# MASTER.net
KiCad netlist of a schematic drawn in EAGLE
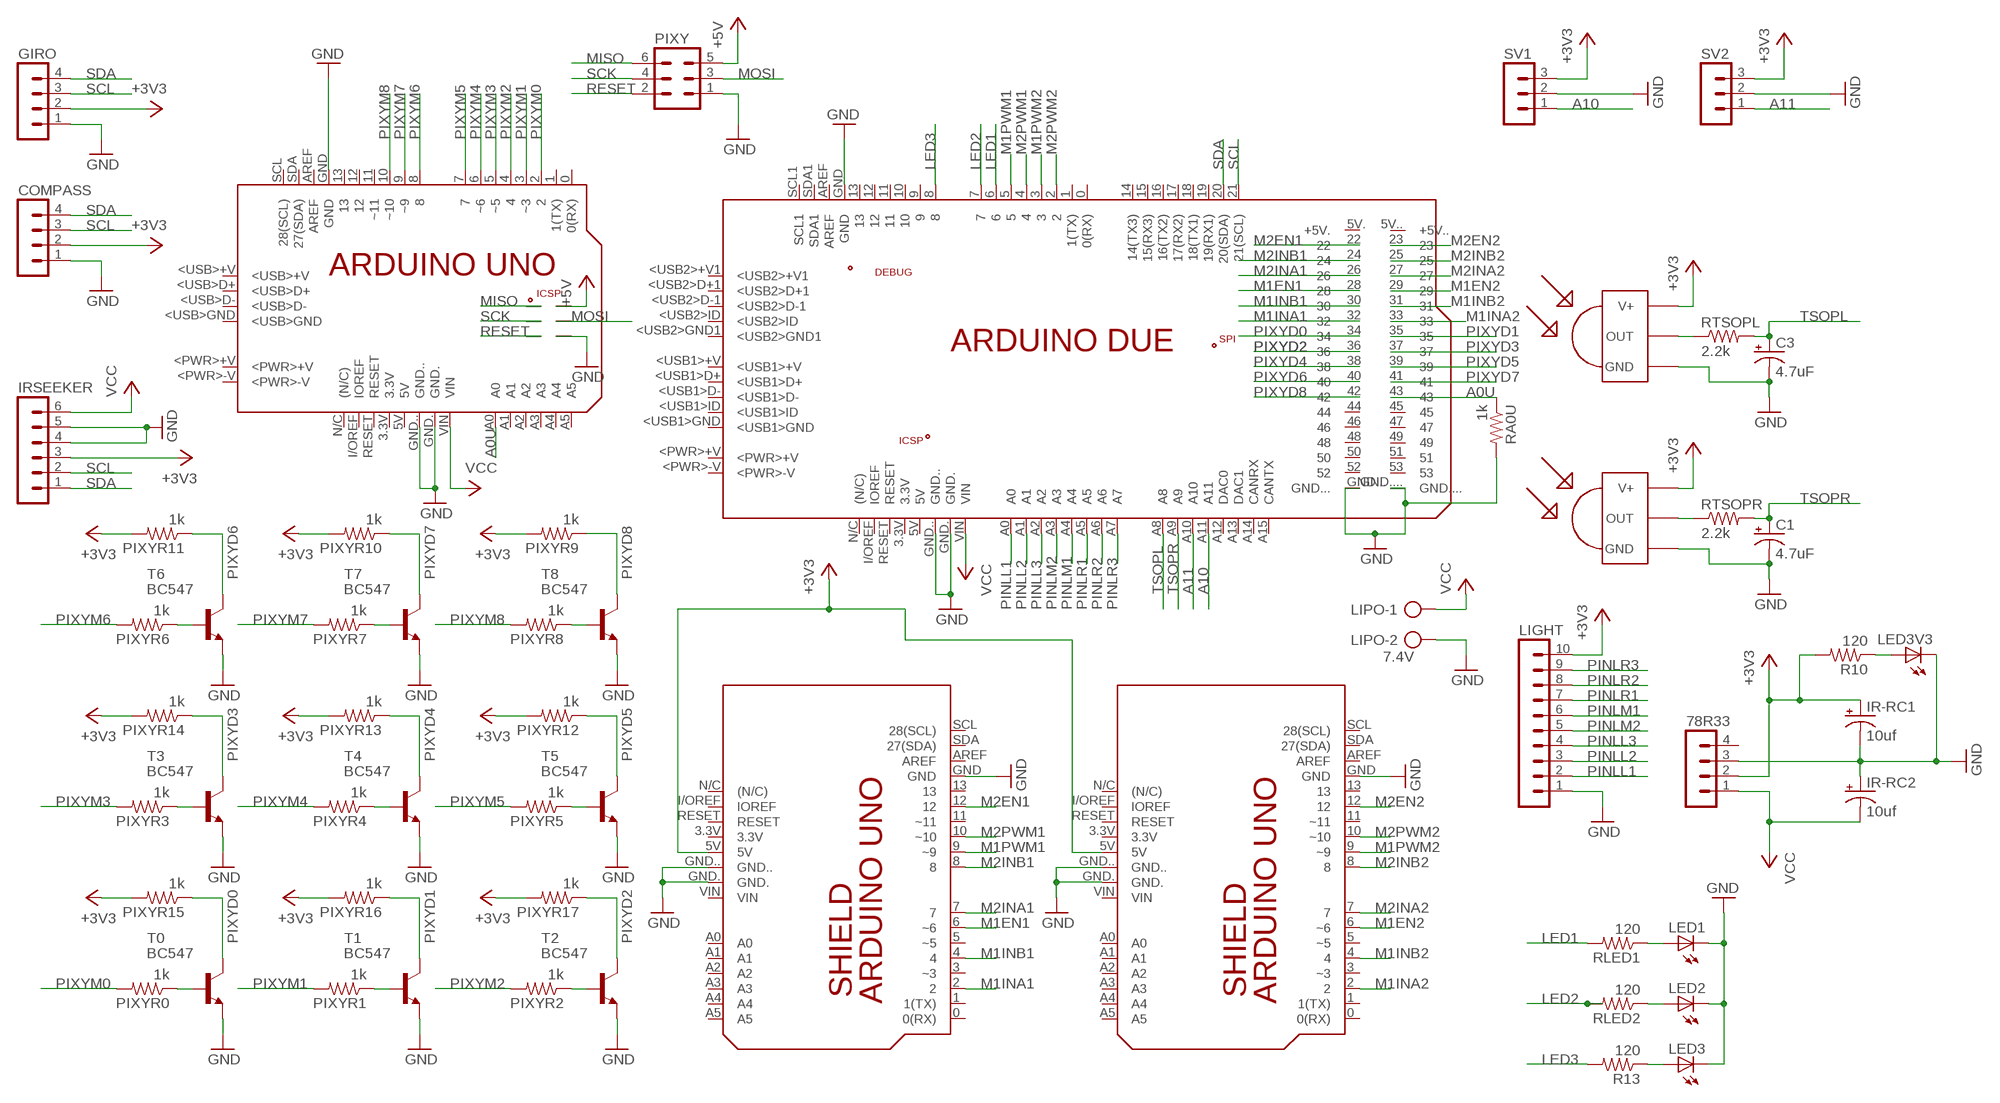
[diagram p0: schematic, sheet 1]

(export (version "E")
  (design (tool "Eeschema 10.0.6"))
  (components
    (comp (ref "78R33")
      (value "MA04-1")
      (footprint "eagle-import:MA04-1")
      (libsource (lib "eagle-import") (part "MA04-1"))
    )
    (comp (ref "C1")
      (value "4.7uF")
      (footprint "eagle-import:E5-6")
      (libsource (lib "eagle-import") (part "CPOL-USE5-6"))
    )
    (comp (ref "C3")
      (value "4.7uF")
      (footprint "eagle-import:E5-6")
      (libsource (lib "eagle-import") (part "CPOL-USE5-6"))
    )
    (comp (ref "COMPASS")
      (value "MA04-1")
      (footprint "eagle-import:MA04-1")
      (libsource (lib "eagle-import") (part "MA04-1"))
    )
    (comp (ref "GIRO")
      (value "MA04-1")
      (footprint "eagle-import:MA04-1")
      (libsource (lib "eagle-import") (part "MA04-1"))
    )
    (comp (ref "IR-RC1")
      (value "10uf")
      (footprint "eagle-import:E5-6")
      (libsource (lib "eagle-import") (part "CPOL-USE5-6"))
    )
    (comp (ref "IR-RC2")
      (value "10uf")
      (footprint "eagle-import:E5-6")
      (libsource (lib "eagle-import") (part "CPOL-USE5-6"))
    )
    (comp (ref "IRSEEKER")
      (value "MA06-1")
      (footprint "eagle-import:MA06-1")
      (libsource (lib "eagle-import") (part "MA06-1"))
    )
    (comp (ref "LED1")
      (value "LED5MM")
      (footprint "eagle-import:LED5MM")
      (libsource (lib "eagle-import") (part "LED5MM"))
    )
    (comp (ref "LED2")
      (value "LED5MM")
      (footprint "eagle-import:LED5MM")
      (libsource (lib "eagle-import") (part "LED5MM"))
    )
    (comp (ref "LED3")
      (value "LED5MM")
      (footprint "eagle-import:LED5MM")
      (libsource (lib "eagle-import") (part "LED5MM"))
    )
    (comp (ref "LED3V3")
      (value "LED5MM")
      (footprint "eagle-import:LED5MM")
      (libsource (lib "eagle-import") (part "LED5MM"))
    )
    (comp (ref "LIGHT")
      (value "MA10-1")
      (footprint "eagle-import:MA10-1")
      (libsource (lib "eagle-import") (part "MA10-1"))
    )
    (comp (ref "LIPO")
      (value "7.4V")
      (footprint "eagle-import:AK500_2")
      (libsource (lib "eagle-import") (part "AK500/2"))
    )
    (comp (ref "PCB3")
      (value "ARDUINO_DUE")
      (footprint "eagle-import:ARDUINO_DUE")
      (libsource (lib "eagle-import") (part "ARDUINO_DUE"))
    )
    (comp (ref "PCB4")
      (value "ARDUINO_UNO")
      (footprint "eagle-import:ARDUINO_UNO")
      (libsource (lib "eagle-import") (part "ARDUINO_UNO"))
    )
    (comp (ref "PIXY")
      (value "MA03-2")
      (footprint "eagle-import:MA03-2")
      (libsource (lib "eagle-import") (part "MA03-2"))
    )
    (comp (ref "PIXYR0")
      (value "1k")
      (footprint "eagle-import:0411_15")
      (libsource (lib "eagle-import") (part "R-US_0411/15"))
    )
    (comp (ref "PIXYR1")
      (value "1k")
      (footprint "eagle-import:0411_15")
      (libsource (lib "eagle-import") (part "R-US_0411/15"))
    )
    (comp (ref "PIXYR2")
      (value "1k")
      (footprint "eagle-import:0411_15")
      (libsource (lib "eagle-import") (part "R-US_0411/15"))
    )
    (comp (ref "PIXYR3")
      (value "1k")
      (footprint "eagle-import:0411_15")
      (libsource (lib "eagle-import") (part "R-US_0411/15"))
    )
    (comp (ref "PIXYR4")
      (value "1k")
      (footprint "eagle-import:0411_15")
      (libsource (lib "eagle-import") (part "R-US_0411/15"))
    )
    (comp (ref "PIXYR5")
      (value "1k")
      (footprint "eagle-import:0411_15")
      (libsource (lib "eagle-import") (part "R-US_0411/15"))
    )
    (comp (ref "PIXYR6")
      (value "1k")
      (footprint "eagle-import:0411_15")
      (libsource (lib "eagle-import") (part "R-US_0411/15"))
    )
    (comp (ref "PIXYR7")
      (value "1k")
      (footprint "eagle-import:0411_15")
      (libsource (lib "eagle-import") (part "R-US_0411/15"))
    )
    (comp (ref "PIXYR8")
      (value "1k")
      (footprint "eagle-import:0411_15")
      (libsource (lib "eagle-import") (part "R-US_0411/15"))
    )
    (comp (ref "PIXYR9")
      (value "1k")
      (footprint "eagle-import:0411_15")
      (libsource (lib "eagle-import") (part "R-US_0411/15"))
    )
    (comp (ref "PIXYR10")
      (value "1k")
      (footprint "eagle-import:0411_15")
      (libsource (lib "eagle-import") (part "R-US_0411/15"))
    )
    (comp (ref "PIXYR11")
      (value "1k")
      (footprint "eagle-import:0411_15")
      (libsource (lib "eagle-import") (part "R-US_0411/15"))
    )
    (comp (ref "PIXYR12")
      (value "1k")
      (footprint "eagle-import:0411_15")
      (libsource (lib "eagle-import") (part "R-US_0411/15"))
    )
    (comp (ref "PIXYR13")
      (value "1k")
      (footprint "eagle-import:0411_15")
      (libsource (lib "eagle-import") (part "R-US_0411/15"))
    )
    (comp (ref "PIXYR14")
      (value "1k")
      (footprint "eagle-import:0411_15")
      (libsource (lib "eagle-import") (part "R-US_0411/15"))
    )
    (comp (ref "PIXYR15")
      (value "1k")
      (footprint "eagle-import:0411_15")
      (libsource (lib "eagle-import") (part "R-US_0411/15"))
    )
    (comp (ref "PIXYR16")
      (value "1k")
      (footprint "eagle-import:0411_15")
      (libsource (lib "eagle-import") (part "R-US_0411/15"))
    )
    (comp (ref "PIXYR17")
      (value "1k")
      (footprint "eagle-import:0411_15")
      (libsource (lib "eagle-import") (part "R-US_0411/15"))
    )
    (comp (ref "PUENTE")
      (value "SHIELD_UNO")
      (footprint "eagle-import:SHIELD_UNO")
      (libsource (lib "eagle-import") (part "SHIELD_UNO"))
    )
    (comp (ref "PUENTE2")
      (value "SHIELD_UNO")
      (footprint "eagle-import:SHIELD_UNO")
      (libsource (lib "eagle-import") (part "SHIELD_UNO"))
    )
    (comp (ref "R10")
      (value "120")
      (footprint "eagle-import:0411_15")
      (libsource (lib "eagle-import") (part "R-US_0411/15"))
    )
    (comp (ref "R13")
      (value "120")
      (footprint "eagle-import:0411_15")
      (libsource (lib "eagle-import") (part "R-US_0411/15"))
    )
    (comp (ref "RA0U")
      (value "1k")
      (footprint "eagle-import:0411_15")
      (libsource (lib "eagle-import") (part "R-US_0411/15"))
    )
    (comp (ref "RLED1")
      (value "120")
      (footprint "eagle-import:0411_15")
      (libsource (lib "eagle-import") (part "R-US_0411/15"))
    )
    (comp (ref "RLED2")
      (value "120")
      (footprint "eagle-import:0411_15")
      (libsource (lib "eagle-import") (part "R-US_0411/15"))
    )
    (comp (ref "RTSOPL")
      (value "2.2k")
      (footprint "eagle-import:0411_15")
      (libsource (lib "eagle-import") (part "R-US_0411/15"))
    )
    (comp (ref "RTSOPR")
      (value "2.2k")
      (footprint "eagle-import:0411_15")
      (libsource (lib "eagle-import") (part "R-US_0411/15"))
    )
    (comp (ref "SV1")
      (value "MA03-1")
      (footprint "eagle-import:MA03-1")
      (libsource (lib "eagle-import") (part "MA03-1"))
    )
    (comp (ref "SV2")
      (value "MA03-1")
      (footprint "eagle-import:MA03-1")
      (libsource (lib "eagle-import") (part "MA03-1"))
    )
    (comp (ref "T0")
      (value "BC547")
      (footprint "eagle-import:TO92")
      (libsource (lib "eagle-import") (part "BC547"))
    )
    (comp (ref "T1")
      (value "BC547")
      (footprint "eagle-import:TO92")
      (libsource (lib "eagle-import") (part "BC547"))
    )
    (comp (ref "T2")
      (value "BC547")
      (footprint "eagle-import:TO92")
      (libsource (lib "eagle-import") (part "BC547"))
    )
    (comp (ref "T3")
      (value "BC547")
      (footprint "eagle-import:TO92")
      (libsource (lib "eagle-import") (part "BC547"))
    )
    (comp (ref "T4")
      (value "BC547")
      (footprint "eagle-import:TO92")
      (libsource (lib "eagle-import") (part "BC547"))
    )
    (comp (ref "T5")
      (value "BC547")
      (footprint "eagle-import:TO92")
      (libsource (lib "eagle-import") (part "BC547"))
    )
    (comp (ref "T6")
      (value "BC547")
      (footprint "eagle-import:TO92")
      (libsource (lib "eagle-import") (part "BC547"))
    )
    (comp (ref "T7")
      (value "BC547")
      (footprint "eagle-import:TO92")
      (libsource (lib "eagle-import") (part "BC547"))
    )
    (comp (ref "T8")
      (value "BC547")
      (footprint "eagle-import:TO92")
      (libsource (lib "eagle-import") (part "BC547"))
    )
    (comp (ref "TSOPL")
      (value "TSOP2240")
      (footprint "eagle-import:TSOP22XX")
      (libsource (lib "eagle-import") (part "TSOP2240"))
    )
    (comp (ref "TSOPR")
      (value "TSOP2240")
      (footprint "eagle-import:TSOP22XX")
      (libsource (lib "eagle-import") (part "TSOP2240"))
    )
  )
  (nets
    (net (code "1") (name "+3V3") (class "Default")
      (node (ref "78R33") (pin "2") (pinfunction "2_2") (pintype "passive"))
      (node (ref "COMPASS") (pin "2") (pinfunction "2_2") (pintype "passive"))
      (node (ref "GIRO") (pin "2") (pinfunction "2_2") (pintype "passive"))
      (node (ref "IR-RC1") (pin "+") (pinfunction "+_+") (pintype "passive"))
      (node (ref "IRSEEKER") (pin "3") (pinfunction "3_3") (pintype "passive"))
      (node (ref "LIGHT") (pin "10") (pinfunction "10_10") (pintype "passive"))
      (node (ref "PIXYR10") (pin "2") (pinfunction "2_2") (pintype "passive"))
      (node (ref "PIXYR11") (pin "2") (pinfunction "2_2") (pintype "passive"))
      (node (ref "PIXYR12") (pin "2") (pinfunction "2_2") (pintype "passive"))
      (node (ref "PIXYR13") (pin "2") (pinfunction "2_2") (pintype "passive"))
      (node (ref "PIXYR14") (pin "2") (pinfunction "2_2") (pintype "passive"))
      (node (ref "PIXYR15") (pin "2") (pinfunction "2_2") (pintype "passive"))
      (node (ref "PIXYR16") (pin "2") (pinfunction "2_2") (pintype "passive"))
      (node (ref "PIXYR17") (pin "2") (pinfunction "2_2") (pintype "passive"))
      (node (ref "PIXYR9") (pin "2") (pinfunction "2_2") (pintype "passive"))
      (node (ref "PUENTE") (pin "5V") (pinfunction "5V_5V") (pintype "bidirectional"))
      (node (ref "PUENTE2") (pin "5V") (pinfunction "5V_5V") (pintype "bidirectional"))
      (node (ref "R10") (pin "2") (pinfunction "2_2") (pintype "passive"))
      (node (ref "SV1") (pin "3") (pinfunction "3_3") (pintype "passive"))
      (node (ref "SV2") (pin "3") (pinfunction "3_3") (pintype "passive"))
      (node (ref "TSOPL") (pin "VCC") (pinfunction "V+_VCC") (pintype "bidirectional"))
      (node (ref "TSOPR") (pin "VCC") (pinfunction "V+_VCC") (pintype "bidirectional"))
    )
    (net (code "2") (name "+5V") (class "Default")
      (node (ref "PCB4") (pin "+5V") (pinfunction "+5V_+5V") (pintype "bidirectional"))
      (node (ref "PIXY") (pin "5") (pinfunction "5_5") (pintype "passive"))
    )
    (net (code "3") (name "/A0U") (class "Default")
      (node (ref "PCB3") (pin "43") (pinfunction "43_43") (pintype "bidirectional"))
      (node (ref "PCB4") (pin "A0") (pinfunction "A0_A0") (pintype "bidirectional"))
      (node (ref "RA0U") (pin "1") (pinfunction "1_1") (pintype "passive"))
    )
    (net (code "4") (name "/A10") (class "Default")
      (node (ref "PCB3") (pin "A11") (pinfunction "A11_A11") (pintype "bidirectional"))
      (node (ref "SV1") (pin "1") (pinfunction "1_1") (pintype "passive"))
    )
    (net (code "5") (name "/A11") (class "Default")
      (node (ref "PCB3") (pin "A10") (pinfunction "A10_A10") (pintype "bidirectional"))
      (node (ref "SV2") (pin "1") (pinfunction "1_1") (pintype "passive"))
    )
    (net (code "6") (name "/LED1") (class "Default")
      (node (ref "PCB3") (pin "6") (pinfunction "6_6") (pintype "bidirectional"))
      (node (ref "RLED1") (pin "2") (pinfunction "2_2") (pintype "passive"))
    )
    (net (code "7") (name "/LED2") (class "Default")
      (node (ref "PCB3") (pin "7") (pinfunction "7_7") (pintype "bidirectional"))
      (node (ref "RLED2") (pin "2") (pinfunction "2_2") (pintype "passive"))
    )
    (net (code "8") (name "/LED3") (class "Default")
      (node (ref "PCB3") (pin "8") (pinfunction "8_8") (pintype "bidirectional"))
      (node (ref "R13") (pin "2") (pinfunction "2_2") (pintype "passive"))
    )
    (net (code "9") (name "/M1EN1") (class "Default")
      (node (ref "PCB3") (pin "28") (pinfunction "28_28") (pintype "bidirectional"))
      (node (ref "PUENTE") (pin "6") (pinfunction "~{6}_6") (pintype "bidirectional"))
    )
    (net (code "10") (name "/M1EN2") (class "Default")
      (node (ref "PCB3") (pin "29") (pinfunction "29_29") (pintype "bidirectional"))
      (node (ref "PUENTE2") (pin "6") (pinfunction "~{6}_6") (pintype "bidirectional"))
    )
    (net (code "11") (name "/M1INA1") (class "Default")
      (node (ref "PCB3") (pin "32") (pinfunction "32_32") (pintype "bidirectional"))
      (node (ref "PUENTE") (pin "2") (pinfunction "2_2") (pintype "bidirectional"))
    )
    (net (code "12") (name "/M1INA2") (class "Default")
      (node (ref "PCB3") (pin "33") (pinfunction "33_33") (pintype "bidirectional"))
      (node (ref "PUENTE2") (pin "2") (pinfunction "2_2") (pintype "bidirectional"))
    )
    (net (code "13") (name "/M1INB1") (class "Default")
      (node (ref "PCB3") (pin "30") (pinfunction "30_30") (pintype "bidirectional"))
      (node (ref "PUENTE") (pin "4") (pinfunction "4_4") (pintype "bidirectional"))
    )
    (net (code "14") (name "/M1INB2") (class "Default")
      (node (ref "PCB3") (pin "31") (pinfunction "31_31") (pintype "bidirectional"))
      (node (ref "PUENTE2") (pin "4") (pinfunction "4_4") (pintype "bidirectional"))
    )
    (net (code "15") (name "/M1PWM1") (class "Default")
      (node (ref "PCB3") (pin "5") (pinfunction "5_5") (pintype "bidirectional"))
      (node (ref "PUENTE") (pin "9") (pinfunction "~{9}_9") (pintype "bidirectional"))
    )
    (net (code "16") (name "/M1PWM2") (class "Default")
      (node (ref "PCB3") (pin "3") (pinfunction "3_3") (pintype "bidirectional"))
      (node (ref "PUENTE2") (pin "9") (pinfunction "~{9}_9") (pintype "bidirectional"))
    )
    (net (code "17") (name "/M2EN1") (class "Default")
      (node (ref "PCB3") (pin "22") (pinfunction "22_22") (pintype "bidirectional"))
      (node (ref "PUENTE") (pin "12") (pinfunction "12_12") (pintype "bidirectional"))
    )
    (net (code "18") (name "/M2EN2") (class "Default")
      (node (ref "PCB3") (pin "23") (pinfunction "23_23") (pintype "bidirectional"))
      (node (ref "PUENTE2") (pin "12") (pinfunction "12_12") (pintype "bidirectional"))
    )
    (net (code "19") (name "/M2INA1") (class "Default")
      (node (ref "PCB3") (pin "26") (pinfunction "26_26") (pintype "bidirectional"))
      (node (ref "PUENTE") (pin "7") (pinfunction "7_7") (pintype "bidirectional"))
    )
    (net (code "20") (name "/M2INA2") (class "Default")
      (node (ref "PCB3") (pin "27") (pinfunction "27_27") (pintype "bidirectional"))
      (node (ref "PUENTE2") (pin "7") (pinfunction "7_7") (pintype "bidirectional"))
    )
    (net (code "21") (name "/M2INB1") (class "Default")
      (node (ref "PCB3") (pin "24") (pinfunction "24_24") (pintype "bidirectional"))
      (node (ref "PUENTE") (pin "8") (pinfunction "8_8") (pintype "bidirectional"))
    )
    (net (code "22") (name "/M2INB2") (class "Default")
      (node (ref "PCB3") (pin "25") (pinfunction "25_25") (pintype "bidirectional"))
      (node (ref "PUENTE2") (pin "8") (pinfunction "8_8") (pintype "bidirectional"))
    )
    (net (code "23") (name "/M2PWM1") (class "Default")
      (node (ref "PCB3") (pin "4") (pinfunction "4_4") (pintype "bidirectional"))
      (node (ref "PUENTE") (pin "10") (pinfunction "~{10}_10") (pintype "bidirectional"))
    )
    (net (code "24") (name "/M2PWM2") (class "Default")
      (node (ref "PCB3") (pin "2") (pinfunction "2_2") (pintype "bidirectional"))
      (node (ref "PUENTE2") (pin "10") (pinfunction "~{10}_10") (pintype "bidirectional"))
    )
    (net (code "25") (name "/MISO") (class "Default")
      (node (ref "PCB4") (pin "MISO") (pinfunction "MISO_MISO") (pintype "bidirectional"))
      (node (ref "PIXY") (pin "6") (pinfunction "6_6") (pintype "passive"))
    )
    (net (code "26") (name "/MOSI") (class "Default")
      (node (ref "PCB4") (pin "MOSI") (pinfunction "MOSI_MOSI") (pintype "bidirectional"))
      (node (ref "PIXY") (pin "3") (pinfunction "3_3") (pintype "passive"))
    )
    (net (code "27") (name "/PINLL1") (class "Default")
      (node (ref "LIGHT") (pin "2") (pinfunction "2_2") (pintype "passive"))
      (node (ref "PCB3") (pin "A0") (pinfunction "A0_A0") (pintype "bidirectional"))
    )
    (net (code "28") (name "/PINLL2") (class "Default")
      (node (ref "LIGHT") (pin "3") (pinfunction "3_3") (pintype "passive"))
      (node (ref "PCB3") (pin "A1") (pinfunction "A1_A1") (pintype "bidirectional"))
    )
    (net (code "29") (name "/PINLL3") (class "Default")
      (node (ref "LIGHT") (pin "4") (pinfunction "4_4") (pintype "passive"))
      (node (ref "PCB3") (pin "A2") (pinfunction "A2_A2") (pintype "bidirectional"))
    )
    (net (code "30") (name "/PINLM1") (class "Default")
      (node (ref "LIGHT") (pin "6") (pinfunction "6_6") (pintype "passive"))
      (node (ref "PCB3") (pin "A4") (pinfunction "A4_A4") (pintype "bidirectional"))
    )
    (net (code "31") (name "/PINLM2") (class "Default")
      (node (ref "LIGHT") (pin "5") (pinfunction "5_5") (pintype "passive"))
      (node (ref "PCB3") (pin "A3") (pinfunction "A3_A3") (pintype "bidirectional"))
    )
    (net (code "32") (name "/PINLR1") (class "Default")
      (node (ref "LIGHT") (pin "7") (pinfunction "7_7") (pintype "passive"))
      (node (ref "PCB3") (pin "A5") (pinfunction "A5_A5") (pintype "bidirectional"))
    )
    (net (code "33") (name "/PINLR2") (class "Default")
      (node (ref "LIGHT") (pin "8") (pinfunction "8_8") (pintype "passive"))
      (node (ref "PCB3") (pin "A6") (pinfunction "A6_A6") (pintype "bidirectional"))
    )
    (net (code "34") (name "/PINLR3") (class "Default")
      (node (ref "LIGHT") (pin "9") (pinfunction "9_9") (pintype "passive"))
      (node (ref "PCB3") (pin "A7") (pinfunction "A7_A7") (pintype "bidirectional"))
    )
    (net (code "35") (name "/PIXYD0") (class "Default")
      (node (ref "PCB3") (pin "34") (pinfunction "34_34") (pintype "bidirectional"))
      (node (ref "PIXYR15") (pin "1") (pinfunction "1_1") (pintype "passive"))
      (node (ref "T0") (pin "3") (pinfunction "C_3") (pintype "passive"))
    )
    (net (code "36") (name "/PIXYD1") (class "Default")
      (node (ref "PCB3") (pin "35") (pinfunction "35_35") (pintype "bidirectional"))
      (node (ref "PIXYR16") (pin "1") (pinfunction "1_1") (pintype "passive"))
      (node (ref "T1") (pin "3") (pinfunction "C_3") (pintype "passive"))
    )
    (net (code "37") (name "/PIXYD2") (class "Default")
      (node (ref "PCB3") (pin "36") (pinfunction "36_36") (pintype "bidirectional"))
      (node (ref "PIXYR17") (pin "1") (pinfunction "1_1") (pintype "passive"))
      (node (ref "T2") (pin "3") (pinfunction "C_3") (pintype "passive"))
    )
    (net (code "38") (name "/PIXYD3") (class "Default")
      (node (ref "PCB3") (pin "37") (pinfunction "37_37") (pintype "bidirectional"))
      (node (ref "PIXYR14") (pin "1") (pinfunction "1_1") (pintype "passive"))
      (node (ref "T3") (pin "3") (pinfunction "C_3") (pintype "passive"))
    )
    (net (code "39") (name "/PIXYD4") (class "Default")
      (node (ref "PCB3") (pin "38") (pinfunction "38_38") (pintype "bidirectional"))
      (node (ref "PIXYR13") (pin "1") (pinfunction "1_1") (pintype "passive"))
      (node (ref "T4") (pin "3") (pinfunction "C_3") (pintype "passive"))
    )
    (net (code "40") (name "/PIXYD5") (class "Default")
      (node (ref "PCB3") (pin "39") (pinfunction "39_39") (pintype "bidirectional"))
      (node (ref "PIXYR12") (pin "1") (pinfunction "1_1") (pintype "passive"))
      (node (ref "T5") (pin "3") (pinfunction "C_3") (pintype "passive"))
    )
    (net (code "41") (name "/PIXYD6") (class "Default")
      (node (ref "PCB3") (pin "40") (pinfunction "40_40") (pintype "bidirectional"))
      (node (ref "PIXYR11") (pin "1") (pinfunction "1_1") (pintype "passive"))
      (node (ref "T6") (pin "3") (pinfunction "C_3") (pintype "passive"))
    )
    (net (code "42") (name "/PIXYD7") (class "Default")
      (node (ref "PCB3") (pin "41") (pinfunction "41_41") (pintype "bidirectional"))
      (node (ref "PIXYR10") (pin "1") (pinfunction "1_1") (pintype "passive"))
      (node (ref "T7") (pin "3") (pinfunction "C_3") (pintype "passive"))
    )
    (net (code "43") (name "/PIXYD8") (class "Default")
      (node (ref "PCB3") (pin "42") (pinfunction "42_42") (pintype "bidirectional"))
      (node (ref "PIXYR9") (pin "1") (pinfunction "1_1") (pintype "passive"))
      (node (ref "T8") (pin "3") (pinfunction "C_3") (pintype "passive"))
    )
    (net (code "44") (name "/PIXYM0") (class "Default")
      (node (ref "PCB4") (pin "2") (pinfunction "2_2") (pintype "bidirectional"))
      (node (ref "PIXYR0") (pin "2") (pinfunction "2_2") (pintype "passive"))
    )
    (net (code "45") (name "/PIXYM1") (class "Default")
      (node (ref "PCB4") (pin "3") (pinfunction "~{3}_3") (pintype "bidirectional"))
      (node (ref "PIXYR1") (pin "2") (pinfunction "2_2") (pintype "passive"))
    )
    (net (code "46") (name "/PIXYM2") (class "Default")
      (node (ref "PCB4") (pin "4") (pinfunction "4_4") (pintype "bidirectional"))
      (node (ref "PIXYR2") (pin "2") (pinfunction "2_2") (pintype "passive"))
    )
    (net (code "47") (name "/PIXYM3") (class "Default")
      (node (ref "PCB4") (pin "5") (pinfunction "~{5}_5") (pintype "bidirectional"))
      (node (ref "PIXYR3") (pin "2") (pinfunction "2_2") (pintype "passive"))
    )
    (net (code "48") (name "/PIXYM4") (class "Default")
      (node (ref "PCB4") (pin "6") (pinfunction "~{6}_6") (pintype "bidirectional"))
      (node (ref "PIXYR4") (pin "2") (pinfunction "2_2") (pintype "passive"))
    )
    (net (code "49") (name "/PIXYM5") (class "Default")
      (node (ref "PCB4") (pin "7") (pinfunction "7_7") (pintype "bidirectional"))
      (node (ref "PIXYR5") (pin "2") (pinfunction "2_2") (pintype "passive"))
    )
    (net (code "50") (name "/PIXYM6") (class "Default")
      (node (ref "PCB4") (pin "8") (pinfunction "8_8") (pintype "bidirectional"))
      (node (ref "PIXYR6") (pin "2") (pinfunction "2_2") (pintype "passive"))
    )
    (net (code "51") (name "/PIXYM7") (class "Default")
      (node (ref "PCB4") (pin "9") (pinfunction "~{9}_9") (pintype "bidirectional"))
      (node (ref "PIXYR7") (pin "2") (pinfunction "2_2") (pintype "passive"))
    )
    (net (code "52") (name "/PIXYM8") (class "Default")
      (node (ref "PCB4") (pin "10") (pinfunction "~{10}_10") (pintype "bidirectional"))
      (node (ref "PIXYR8") (pin "2") (pinfunction "2_2") (pintype "passive"))
    )
    (net (code "53") (name "/RESET") (class "Default")
      (node (ref "PCB4") (pin "RESET.") (pinfunction "RESET._RESET.") (pintype "bidirectional"))
      (node (ref "PIXY") (pin "2") (pinfunction "2_2") (pintype "passive"))
    )
    (net (code "54") (name "/SCK") (class "Default")
      (node (ref "PCB4") (pin "SCK") (pinfunction "SCK_SCK") (pintype "bidirectional"))
      (node (ref "PIXY") (pin "4") (pinfunction "4_4") (pintype "passive"))
    )
    (net (code "55") (name "/SCL") (class "Default")
      (node (ref "COMPASS") (pin "3") (pinfunction "3_3") (pintype "passive"))
      (node (ref "GIRO") (pin "3") (pinfunction "3_3") (pintype "passive"))
      (node (ref "IRSEEKER") (pin "2") (pinfunction "2_2") (pintype "passive"))
      (node (ref "PCB3") (pin "21") (pinfunction "21(SCL)_21") (pintype "bidirectional"))
    )
    (net (code "56") (name "/SDA") (class "Default")
      (node (ref "COMPASS") (pin "4") (pinfunction "4_4") (pintype "passive"))
      (node (ref "GIRO") (pin "4") (pinfunction "4_4") (pintype "passive"))
      (node (ref "IRSEEKER") (pin "1") (pinfunction "1_1") (pintype "passive"))
      (node (ref "PCB3") (pin "20") (pinfunction "20(SDA)_20") (pintype "bidirectional"))
    )
    (net (code "57") (name "/TSOPL") (class "Default")
      (node (ref "C3") (pin "+") (pinfunction "+_+") (pintype "passive"))
      (node (ref "PCB3") (pin "A8") (pinfunction "A8_A8") (pintype "bidirectional"))
      (node (ref "RTSOPL") (pin "2") (pinfunction "2_2") (pintype "passive"))
    )
    (net (code "58") (name "/TSOPR") (class "Default")
      (node (ref "C1") (pin "+") (pinfunction "+_+") (pintype "passive"))
      (node (ref "PCB3") (pin "A9") (pinfunction "A9_A9") (pintype "bidirectional"))
      (node (ref "RTSOPR") (pin "2") (pinfunction "2_2") (pintype "passive"))
    )
    (net (code "59") (name "GND") (class "Default")
      (node (ref "78R33") (pin "3") (pinfunction "3_3") (pintype "passive"))
      (node (ref "C1") (pin "-") (pinfunction "-_-") (pintype "passive"))
      (node (ref "C3") (pin "-") (pinfunction "-_-") (pintype "passive"))
      (node (ref "COMPASS") (pin "1") (pinfunction "1_1") (pintype "passive"))
      (node (ref "GIRO") (pin "1") (pinfunction "1_1") (pintype "passive"))
      (node (ref "IR-RC1") (pin "-") (pinfunction "-_-") (pintype "passive"))
      (node (ref "IR-RC2") (pin "+") (pinfunction "+_+") (pintype "passive"))
      (node (ref "IRSEEKER") (pin "4") (pinfunction "4_4") (pintype "passive"))
      (node (ref "IRSEEKER") (pin "5") (pinfunction "5_5") (pintype "passive"))
      (node (ref "LED1") (pin "K") (pinfunction "C_K") (pintype "passive"))
      (node (ref "LED2") (pin "K") (pinfunction "C_K") (pintype "passive"))
      (node (ref "LED3") (pin "K") (pinfunction "C_K") (pintype "passive"))
      (node (ref "LED3V3") (pin "K") (pinfunction "C_K") (pintype "passive"))
      (node (ref "LIGHT") (pin "1") (pinfunction "1_1") (pintype "passive"))
      (node (ref "LIPO") (pin "2") (pinfunction "KL_2") (pintype "passive"))
      (node (ref "PCB3") (pin "GND") (pinfunction "GND_GND") (pintype "bidirectional"))
      (node (ref "PCB3") (pin "GND.") (pinfunction "GND._GND.") (pintype "bidirectional"))
      (node (ref "PCB3") (pin "GND..") (pinfunction "GND.._GND..") (pintype "bidirectional"))
      (node (ref "PCB3") (pin "GND...") (pinfunction "GND..._GND...") (pintype "bidirectional"))
      (node (ref "PCB3") (pin "GND....") (pinfunction "GND...._GND....") (pintype "bidirectional"))
      (node (ref "PCB4") (pin "GND") (pinfunction "GND_GND") (pintype "bidirectional"))
      (node (ref "PCB4") (pin "GND.") (pinfunction "GND._GND.") (pintype "bidirectional"))
      (node (ref "PCB4") (pin "GND..") (pinfunction "GND.._GND..") (pintype "bidirectional"))
      (node (ref "PCB4") (pin "GND_") (pinfunction "GND__GND_") (pintype "bidirectional"))
      (node (ref "PIXY") (pin "1") (pinfunction "1_1") (pintype "passive"))
      (node (ref "PUENTE") (pin "GND") (pinfunction "GND_GND") (pintype "bidirectional"))
      (node (ref "PUENTE") (pin "GND.") (pinfunction "GND._GND.") (pintype "bidirectional"))
      (node (ref "PUENTE") (pin "GND..") (pinfunction "GND.._GND..") (pintype "bidirectional"))
      (node (ref "PUENTE2") (pin "GND") (pinfunction "GND_GND") (pintype "bidirectional"))
      (node (ref "PUENTE2") (pin "GND.") (pinfunction "GND._GND.") (pintype "bidirectional"))
      (node (ref "PUENTE2") (pin "GND..") (pinfunction "GND.._GND..") (pintype "bidirectional"))
      (node (ref "RA0U") (pin "2") (pinfunction "2_2") (pintype "passive"))
      (node (ref "SV1") (pin "2") (pinfunction "2_2") (pintype "passive"))
      (node (ref "SV2") (pin "2") (pinfunction "2_2") (pintype "passive"))
      (node (ref "T0") (pin "1") (pinfunction "E_1") (pintype "passive"))
      (node (ref "T1") (pin "1") (pinfunction "E_1") (pintype "passive"))
      (node (ref "T2") (pin "1") (pinfunction "E_1") (pintype "passive"))
      (node (ref "T3") (pin "1") (pinfunction "E_1") (pintype "passive"))
      (node (ref "T4") (pin "1") (pinfunction "E_1") (pintype "passive"))
      (node (ref "T5") (pin "1") (pinfunction "E_1") (pintype "passive"))
      (node (ref "T6") (pin "1") (pinfunction "E_1") (pintype "passive"))
      (node (ref "T7") (pin "1") (pinfunction "E_1") (pintype "passive"))
      (node (ref "T8") (pin "1") (pinfunction "E_1") (pintype "passive"))
      (node (ref "TSOPL") (pin "GND") (pinfunction "GND_GND") (pintype "bidirectional"))
      (node (ref "TSOPR") (pin "GND") (pinfunction "GND_GND") (pintype "bidirectional"))
    )
    (net (code "60") (name "Net-(LED1-PadA)") (class "Default")
      (node (ref "LED1") (pin "A") (pinfunction "A_A") (pintype "passive"))
      (node (ref "RLED1") (pin "1") (pinfunction "1_1") (pintype "passive"))
    )
    (net (code "61") (name "Net-(LED2-PadA)") (class "Default")
      (node (ref "LED2") (pin "A") (pinfunction "A_A") (pintype "passive"))
      (node (ref "RLED2") (pin "1") (pinfunction "1_1") (pintype "passive"))
    )
    (net (code "62") (name "Net-(LED3-PadA)") (class "Default")
      (node (ref "LED3") (pin "A") (pinfunction "A_A") (pintype "passive"))
      (node (ref "R13") (pin "1") (pinfunction "1_1") (pintype "passive"))
    )
    (net (code "63") (name "Net-(LED3V3-PadA)") (class "Default")
      (node (ref "LED3V3") (pin "A") (pinfunction "A_A") (pintype "passive"))
      (node (ref "R10") (pin "1") (pinfunction "1_1") (pintype "passive"))
    )
    (net (code "64") (name "Net-(RTSOPL-Pad1)") (class "Default")
      (node (ref "RTSOPL") (pin "1") (pinfunction "1_1") (pintype "passive"))
      (node (ref "TSOPL") (pin "OUT") (pinfunction "OUT_OUT") (pintype "bidirectional"))
    )
    (net (code "65") (name "Net-(RTSOPR-Pad1)") (class "Default")
      (node (ref "RTSOPR") (pin "1") (pinfunction "1_1") (pintype "passive"))
      (node (ref "TSOPR") (pin "OUT") (pinfunction "OUT_OUT") (pintype "bidirectional"))
    )
    (net (code "66") (name "Net-(T0-B)") (class "Default")
      (node (ref "PIXYR0") (pin "1") (pinfunction "1_1") (pintype "passive"))
      (node (ref "T0") (pin "2") (pinfunction "B_2") (pintype "passive"))
    )
    (net (code "67") (name "Net-(T1-B)") (class "Default")
      (node (ref "PIXYR1") (pin "1") (pinfunction "1_1") (pintype "passive"))
      (node (ref "T1") (pin "2") (pinfunction "B_2") (pintype "passive"))
    )
    (net (code "68") (name "Net-(T2-B)") (class "Default")
      (node (ref "PIXYR2") (pin "1") (pinfunction "1_1") (pintype "passive"))
      (node (ref "T2") (pin "2") (pinfunction "B_2") (pintype "passive"))
    )
    (net (code "69") (name "Net-(T3-B)") (class "Default")
      (node (ref "PIXYR3") (pin "1") (pinfunction "1_1") (pintype "passive"))
      (node (ref "T3") (pin "2") (pinfunction "B_2") (pintype "passive"))
    )
    (net (code "70") (name "Net-(T4-B)") (class "Default")
      (node (ref "PIXYR4") (pin "1") (pinfunction "1_1") (pintype "passive"))
      (node (ref "T4") (pin "2") (pinfunction "B_2") (pintype "passive"))
    )
    (net (code "71") (name "Net-(T5-B)") (class "Default")
      (node (ref "PIXYR5") (pin "1") (pinfunction "1_1") (pintype "passive"))
      (node (ref "T5") (pin "2") (pinfunction "B_2") (pintype "passive"))
    )
    (net (code "72") (name "Net-(T6-B)") (class "Default")
      (node (ref "PIXYR6") (pin "1") (pinfunction "1_1") (pintype "passive"))
      (node (ref "T6") (pin "2") (pinfunction "B_2") (pintype "passive"))
    )
    (net (code "73") (name "Net-(T7-B)") (class "Default")
      (node (ref "PIXYR7") (pin "1") (pinfunction "1_1") (pintype "passive"))
      (node (ref "T7") (pin "2") (pinfunction "B_2") (pintype "passive"))
    )
    (net (code "74") (name "Net-(T8-B)") (class "Default")
      (node (ref "PIXYR8") (pin "1") (pinfunction "1_1") (pintype "passive"))
      (node (ref "T8") (pin "2") (pinfunction "B_2") (pintype "passive"))
    )
    (net (code "75") (name "VCC") (class "Default")
      (node (ref "78R33") (pin "1") (pinfunction "1_1") (pintype "passive"))
      (node (ref "IR-RC2") (pin "-") (pinfunction "-_-") (pintype "passive"))
      (node (ref "IRSEEKER") (pin "6") (pinfunction "6_6") (pintype "passive"))
      (node (ref "LIPO") (pin "1") (pinfunction "KL_1") (pintype "passive"))
      (node (ref "PCB3") (pin "VIN") (pinfunction "VIN_VIN") (pintype "bidirectional"))
      (node (ref "PCB4") (pin "VIN") (pinfunction "VIN_VIN") (pintype "bidirectional"))
    )
    (net (code "76") (name "unconnected-(78R33-Pad4)") (class "Default")
      (node (ref "78R33") (pin "4") (pinfunction "4_4") (pintype "passive"))
    )
    (net (code "77") (name "unconnected-(PCB3-(N{slash}C)-PadN{slash}C)") (class "Default")
      (node (ref "PCB3") (pin "N/C") (pinfunction "(N/C)_N/C") (pintype "bidirectional"))
    )
    (net (code "78") (name "unconnected-(PCB3-+5V.-Pad5V.)") (class "Default")
      (node (ref "PCB3") (pin "5V.") (pinfunction "+5V._5V.") (pintype "bidirectional"))
    )
    (net (code "79") (name "unconnected-(PCB3-+5V..-Pad5V..)") (class "Default")
      (node (ref "PCB3") (pin "5V..") (pinfunction "+5V.._5V..") (pintype "bidirectional"))
    )
    (net (code "80") (name "unconnected-(PCB3-0(RX)-Pad0)") (class "Default")
      (node (ref "PCB3") (pin "0") (pinfunction "0(RX)_0") (pintype "bidirectional"))
    )
    (net (code "81") (name "unconnected-(PCB3-1(TX)-Pad1)") (class "Default")
      (node (ref "PCB3") (pin "1") (pinfunction "1(TX)_1") (pintype "bidirectional"))
    )
    (net (code "82") (name "unconnected-(PCB3-14(TX3)-Pad14)") (class "Default")
      (node (ref "PCB3") (pin "14") (pinfunction "14(TX3)_14") (pintype "bidirectional"))
    )
    (net (code "83") (name "unconnected-(PCB3-15(RX3)-Pad15)") (class "Default")
      (node (ref "PCB3") (pin "15") (pinfunction "15(RX3)_15") (pintype "bidirectional"))
    )
    (net (code "84") (name "unconnected-(PCB3-16(TX2)-Pad16)") (class "Default")
      (node (ref "PCB3") (pin "16") (pinfunction "16(TX2)_16") (pintype "bidirectional"))
    )
    (net (code "85") (name "unconnected-(PCB3-17(RX2)-Pad17)") (class "Default")
      (node (ref "PCB3") (pin "17") (pinfunction "17(RX2)_17") (pintype "bidirectional"))
    )
    (net (code "86") (name "unconnected-(PCB3-18(TX1)-Pad18)") (class "Default")
      (node (ref "PCB3") (pin "18") (pinfunction "18(TX1)_18") (pintype "bidirectional"))
    )
    (net (code "87") (name "unconnected-(PCB3-19(RX1)-Pad19)") (class "Default")
      (node (ref "PCB3") (pin "19") (pinfunction "19(RX1)_19") (pintype "bidirectional"))
    )
    (net (code "88") (name "unconnected-(PCB3-CANRX-PadA14)") (class "Default")
      (node (ref "PCB3") (pin "A14") (pinfunction "CANRX_A14") (pintype "bidirectional"))
    )
    (net (code "89") (name "unconnected-(PCB3-CANTX-PadA15)") (class "Default")
      (node (ref "PCB3") (pin "A15") (pinfunction "CANTX_A15") (pintype "bidirectional"))
    )
    (net (code "90") (name "unconnected-(PCB3-DAC0-PadA12)") (class "Default")
      (node (ref "PCB3") (pin "A12") (pinfunction "DAC0_A12") (pintype "bidirectional"))
    )
    (net (code "91") (name "unconnected-(PCB3-DAC1-PadA13)") (class "Default")
      (node (ref "PCB3") (pin "A13") (pinfunction "DAC1_A13") (pintype "bidirectional"))
    )
    (net (code "92") (name "unconnected-(PCB3-IOREF-PadI{slash}OREF)") (class "Default")
      (node (ref "PCB3") (pin "I/OREF") (pinfunction "IOREF_I/OREF") (pintype "bidirectional"))
    )
    (net (code "93") (name "unconnected-(PCB3-Pad+5V)") (class "Default")
      (node (ref "PCB3") (pin "+5V") (pinfunction "+5V_+5V") (pintype "bidirectional"))
    )
    (net (code "94") (name "unconnected-(PCB3-Pad+5V_)") (class "Default")
      (node (ref "PCB3") (pin "+5V_") (pinfunction "+5V__+5V_") (pintype "bidirectional"))
    )
    (net (code "95") (name "unconnected-(PCB3-Pad3.3V)") (class "Default")
      (node (ref "PCB3") (pin "3.3V") (pinfunction "3.3V_3.3V") (pintype "bidirectional"))
    )
    (net (code "96") (name "unconnected-(PCB3-Pad5V)") (class "Default")
      (node (ref "PCB3") (pin "5V") (pinfunction "5V_5V") (pintype "bidirectional"))
    )
    (net (code "97") (name "unconnected-(PCB3-Pad9)") (class "Default")
      (node (ref "PCB3") (pin "9") (pinfunction "9_9") (pintype "bidirectional"))
    )
    (net (code "98") (name "unconnected-(PCB3-Pad10)") (class "Default")
      (node (ref "PCB3") (pin "10") (pinfunction "10_10") (pintype "bidirectional"))
    )
    (net (code "99") (name "unconnected-(PCB3-Pad11)") (class "Default")
      (node (ref "PCB3") (pin "11") (pinfunction "11_11") (pintype "bidirectional"))
    )
    (net (code "100") (name "unconnected-(PCB3-Pad12)") (class "Default")
      (node (ref "PCB3") (pin "12") (pinfunction "12_12") (pintype "bidirectional"))
    )
    (net (code "101") (name "unconnected-(PCB3-Pad13)") (class "Default")
      (node (ref "PCB3") (pin "13") (pinfunction "13_13") (pintype "bidirectional"))
    )
    (net (code "102") (name "unconnected-(PCB3-Pad44)") (class "Default")
      (node (ref "PCB3") (pin "44") (pinfunction "44_44") (pintype "bidirectional"))
    )
    (net (code "103") (name "unconnected-(PCB3-Pad45)") (class "Default")
      (node (ref "PCB3") (pin "45") (pinfunction "45_45") (pintype "bidirectional"))
    )
    (net (code "104") (name "unconnected-(PCB3-Pad46)") (class "Default")
      (node (ref "PCB3") (pin "46") (pinfunction "46_46") (pintype "bidirectional"))
    )
    (net (code "105") (name "unconnected-(PCB3-Pad47)") (class "Default")
      (node (ref "PCB3") (pin "47") (pinfunction "47_47") (pintype "bidirectional"))
    )
    (net (code "106") (name "unconnected-(PCB3-Pad48)") (class "Default")
      (node (ref "PCB3") (pin "48") (pinfunction "48_48") (pintype "bidirectional"))
    )
    (net (code "107") (name "unconnected-(PCB3-Pad49)") (class "Default")
      (node (ref "PCB3") (pin "49") (pinfunction "49_49") (pintype "bidirectional"))
    )
    (net (code "108") (name "unconnected-(PCB3-Pad50)") (class "Default")
      (node (ref "PCB3") (pin "50") (pinfunction "50_50") (pintype "bidirectional"))
    )
    (net (code "109") (name "unconnected-(PCB3-Pad51)") (class "Default")
      (node (ref "PCB3") (pin "51") (pinfunction "51_51") (pintype "bidirectional"))
    )
    (net (code "110") (name "unconnected-(PCB3-Pad52)") (class "Default")
      (node (ref "PCB3") (pin "52") (pinfunction "52_52") (pintype "bidirectional"))
    )
    (net (code "111") (name "unconnected-(PCB3-Pad53)") (class "Default")
      (node (ref "PCB3") (pin "53") (pinfunction "53_53") (pintype "bidirectional"))
    )
    (net (code "112") (name "unconnected-(PCB3-Pad<PWR>+V)") (class "Default")
      (node (ref "PCB3") (pin "<PWR>+V") (pinfunction "<PWR>+V_<PWR>+V") (pintype "bidirectional"))
    )
    (net (code "113") (name "unconnected-(PCB3-Pad<PWR>-V)") (class "Default")
      (node (ref "PCB3") (pin "<PWR>-V") (pinfunction "<PWR>-V_<PWR>-V") (pintype "bidirectional"))
    )
    (net (code "114") (name "unconnected-(PCB3-Pad<USB1>+V)") (class "Default")
      (node (ref "PCB3") (pin "<USB1>+V") (pinfunction "<USB1>+V_<USB1>+V") (pintype "bidirectional"))
    )
    (net (code "115") (name "unconnected-(PCB3-Pad<USB1>D+)") (class "Default")
      (node (ref "PCB3") (pin "<USB1>D+") (pinfunction "<USB1>D+_<USB1>D+") (pintype "bidirectional"))
    )
    (net (code "116") (name "unconnected-(PCB3-Pad<USB1>D-)") (class "Default")
      (node (ref "PCB3") (pin "<USB1>D-") (pinfunction "<USB1>D-_<USB1>D-") (pintype "bidirectional"))
    )
    (net (code "117") (name "unconnected-(PCB3-Pad<USB1>GND)") (class "Default")
      (node (ref "PCB3") (pin "<USB1>GND") (pinfunction "<USB1>GND_<USB1>GND") (pintype "bidirectional"))
    )
    (net (code "118") (name "unconnected-(PCB3-Pad<USB1>ID)") (class "Default")
      (node (ref "PCB3") (pin "<USB1>ID") (pinfunction "<USB1>ID_<USB1>ID") (pintype "bidirectional"))
    )
    (net (code "119") (name "unconnected-(PCB3-Pad<USB2>+V1)") (class "Default")
      (node (ref "PCB3") (pin "<USB2>+V1") (pinfunction "<USB2>+V1_<USB2>+V1") (pintype "bidirectional"))
    )
    (net (code "120") (name "unconnected-(PCB3-Pad<USB2>D+1)") (class "Default")
      (node (ref "PCB3") (pin "<USB2>D+1") (pinfunction "<USB2>D+1_<USB2>D+1") (pintype "bidirectional"))
    )
    (net (code "121") (name "unconnected-(PCB3-Pad<USB2>D-1)") (class "Default")
      (node (ref "PCB3") (pin "<USB2>D-1") (pinfunction "<USB2>D-1_<USB2>D-1") (pintype "bidirectional"))
    )
    (net (code "122") (name "unconnected-(PCB3-Pad<USB2>GND1)") (class "Default")
      (node (ref "PCB3") (pin "<USB2>GND1") (pinfunction "<USB2>GND1_<USB2>GND1") (pintype "bidirectional"))
    )
    (net (code "123") (name "unconnected-(PCB3-Pad<USB2>ID)") (class "Default")
      (node (ref "PCB3") (pin "<USB2>ID") (pinfunction "<USB2>ID_<USB2>ID") (pintype "bidirectional"))
    )
    (net (code "124") (name "unconnected-(PCB3-PadAREF)") (class "Default")
      (node (ref "PCB3") (pin "AREF") (pinfunction "AREF_AREF") (pintype "bidirectional"))
    )
    (net (code "125") (name "unconnected-(PCB3-PadGND1)") (class "Default")
      (node (ref "PCB3") (pin "GND1") (pinfunction "GND1_GND1") (pintype "bidirectional"))
    )
    (net (code "126") (name "unconnected-(PCB3-PadGND_)") (class "Default")
      (node (ref "PCB3") (pin "GND_") (pinfunction "GND__GND_") (pintype "bidirectional"))
    )
    (net (code "127") (name "unconnected-(PCB3-PadGND__)") (class "Default")
      (node (ref "PCB3") (pin "GND__") (pinfunction "GND___GND__") (pintype "bidirectional"))
    )
    (net (code "128") (name "unconnected-(PCB3-PadMISO)") (class "Default")
      (node (ref "PCB3") (pin "MISO") (pinfunction "MISO_MISO") (pintype "bidirectional"))
    )
    (net (code "129") (name "unconnected-(PCB3-PadMISO2)") (class "Default")
      (node (ref "PCB3") (pin "MISO2") (pinfunction "MISO2_MISO2") (pintype "bidirectional"))
    )
    (net (code "130") (name "unconnected-(PCB3-PadMOSI)") (class "Default")
      (node (ref "PCB3") (pin "MOSI") (pinfunction "MOSI_MOSI") (pintype "bidirectional"))
    )
    (net (code "131") (name "unconnected-(PCB3-PadMOSI2)") (class "Default")
      (node (ref "PCB3") (pin "MOSI2") (pinfunction "MOSI2_MOSI2") (pintype "bidirectional"))
    )
    (net (code "132") (name "unconnected-(PCB3-PadRESET)") (class "Default")
      (node (ref "PCB3") (pin "RESET") (pinfunction "RESET_RESET") (pintype "bidirectional"))
    )
    (net (code "133") (name "unconnected-(PCB3-PadRESET.)") (class "Default")
      (node (ref "PCB3") (pin "RESET.") (pinfunction "RESET._RESET.") (pintype "bidirectional"))
    )
    (net (code "134") (name "unconnected-(PCB3-PadRESET..)") (class "Default")
      (node (ref "PCB3") (pin "RESET..") (pinfunction "RESET.._RESET..") (pintype "bidirectional"))
    )
    (net (code "135") (name "unconnected-(PCB3-PadRESET2)") (class "Default")
      (node (ref "PCB3") (pin "RESET2") (pinfunction "RESET2_RESET2") (pintype "bidirectional"))
    )
    (net (code "136") (name "unconnected-(PCB3-PadSCK)") (class "Default")
      (node (ref "PCB3") (pin "SCK") (pinfunction "SCK_SCK") (pintype "bidirectional"))
    )
    (net (code "137") (name "unconnected-(PCB3-PadSCK2)") (class "Default")
      (node (ref "PCB3") (pin "SCK2") (pinfunction "SCK2_SCK2") (pintype "bidirectional"))
    )
    (net (code "138") (name "unconnected-(PCB3-PadSCL1)") (class "Default")
      (node (ref "PCB3") (pin "SCL1") (pinfunction "SCL1_SCL1") (pintype "bidirectional"))
    )
    (net (code "139") (name "unconnected-(PCB3-PadSDA1)") (class "Default")
      (node (ref "PCB3") (pin "SDA1") (pinfunction "SDA1_SDA1") (pintype "bidirectional"))
    )
    (net (code "140") (name "unconnected-(PCB3-PadSWCLK)") (class "Default")
      (node (ref "PCB3") (pin "SWCLK") (pinfunction "SWCLK_SWCLK") (pintype "bidirectional"))
    )
    (net (code "141") (name "unconnected-(PCB3-PadSWDIO)") (class "Default")
      (node (ref "PCB3") (pin "SWDIO") (pinfunction "SWDIO_SWDIO") (pintype "bidirectional"))
    )
    (net (code "142") (name "unconnected-(PCB4-(N{slash}C)-PadN{slash}C)") (class "Default")
      (node (ref "PCB4") (pin "N/C") (pinfunction "(N/C)_N/C") (pintype "bidirectional"))
    )
    (net (code "143") (name "unconnected-(PCB4-0(RX)-Pad0)") (class "Default")
      (node (ref "PCB4") (pin "0") (pinfunction "0(RX)_0") (pintype "bidirectional"))
    )
    (net (code "144") (name "unconnected-(PCB4-1(TX)-Pad1)") (class "Default")
      (node (ref "PCB4") (pin "1") (pinfunction "1(TX)_1") (pintype "bidirectional"))
    )
    (net (code "145") (name "unconnected-(PCB4-27(SDA)-PadSDA)") (class "Default")
      (node (ref "PCB4") (pin "SDA") (pinfunction "27(SDA)_SDA") (pintype "bidirectional"))
    )
    (net (code "146") (name "unconnected-(PCB4-28(SCL)-PadSCL)") (class "Default")
      (node (ref "PCB4") (pin "SCL") (pinfunction "28(SCL)_SCL") (pintype "bidirectional"))
    )
    (net (code "147") (name "unconnected-(PCB4-IOREF-PadI{slash}OREF)") (class "Default")
      (node (ref "PCB4") (pin "I/OREF") (pinfunction "IOREF_I/OREF") (pintype "bidirectional"))
    )
    (net (code "148") (name "unconnected-(PCB4-Pad3.3V)") (class "Default")
      (node (ref "PCB4") (pin "3.3V") (pinfunction "3.3V_3.3V") (pintype "bidirectional"))
    )
    (net (code "149") (name "unconnected-(PCB4-Pad5V)") (class "Default")
      (node (ref "PCB4") (pin "5V") (pinfunction "5V_5V") (pintype "bidirectional"))
    )
    (net (code "150") (name "unconnected-(PCB4-Pad12)") (class "Default")
      (node (ref "PCB4") (pin "12") (pinfunction "12_12") (pintype "bidirectional"))
    )
    (net (code "151") (name "unconnected-(PCB4-Pad13)") (class "Default")
      (node (ref "PCB4") (pin "13") (pinfunction "13_13") (pintype "bidirectional"))
    )
    (net (code "152") (name "unconnected-(PCB4-Pad<PWR>+V)") (class "Default")
      (node (ref "PCB4") (pin "<PWR>+V") (pinfunction "<PWR>+V_<PWR>+V") (pintype "bidirectional"))
    )
    (net (code "153") (name "unconnected-(PCB4-Pad<PWR>-V)") (class "Default")
      (node (ref "PCB4") (pin "<PWR>-V") (pinfunction "<PWR>-V_<PWR>-V") (pintype "bidirectional"))
    )
    (net (code "154") (name "unconnected-(PCB4-Pad<USB>+V)") (class "Default")
      (node (ref "PCB4") (pin "<USB>+V") (pinfunction "<USB>+V_<USB>+V") (pintype "bidirectional"))
    )
    (net (code "155") (name "unconnected-(PCB4-Pad<USB>D+)") (class "Default")
      (node (ref "PCB4") (pin "<USB>D+") (pinfunction "<USB>D+_<USB>D+") (pintype "bidirectional"))
    )
    (net (code "156") (name "unconnected-(PCB4-Pad<USB>D-)") (class "Default")
      (node (ref "PCB4") (pin "<USB>D-") (pinfunction "<USB>D-_<USB>D-") (pintype "bidirectional"))
    )
    (net (code "157") (name "unconnected-(PCB4-Pad<USB>GND)") (class "Default")
      (node (ref "PCB4") (pin "<USB>GND") (pinfunction "<USB>GND_<USB>GND") (pintype "bidirectional"))
    )
    (net (code "158") (name "unconnected-(PCB4-PadA1)") (class "Default")
      (node (ref "PCB4") (pin "A1") (pinfunction "A1_A1") (pintype "bidirectional"))
    )
    (net (code "159") (name "unconnected-(PCB4-PadA2)") (class "Default")
      (node (ref "PCB4") (pin "A2") (pinfunction "A2_A2") (pintype "bidirectional"))
    )
    (net (code "160") (name "unconnected-(PCB4-PadA3)") (class "Default")
      (node (ref "PCB4") (pin "A3") (pinfunction "A3_A3") (pintype "bidirectional"))
    )
    (net (code "161") (name "unconnected-(PCB4-PadA4)") (class "Default")
      (node (ref "PCB4") (pin "A4") (pinfunction "A4_A4") (pintype "bidirectional"))
    )
    (net (code "162") (name "unconnected-(PCB4-PadA5)") (class "Default")
      (node (ref "PCB4") (pin "A5") (pinfunction "A5_A5") (pintype "bidirectional"))
    )
    (net (code "163") (name "unconnected-(PCB4-PadAREF)") (class "Default")
      (node (ref "PCB4") (pin "AREF") (pinfunction "AREF_AREF") (pintype "bidirectional"))
    )
    (net (code "164") (name "unconnected-(PCB4-PadRESET)") (class "Default")
      (node (ref "PCB4") (pin "RESET") (pinfunction "RESET_RESET") (pintype "bidirectional"))
    )
    (net (code "165") (name "unconnected-(PCB4-~{11}-Pad11)") (class "Default")
      (node (ref "PCB4") (pin "11") (pinfunction "~{11}_11") (pintype "bidirectional"))
    )
    (net (code "166") (name "unconnected-(PUENTE-(N{slash}C)-PadN{slash}C)") (class "Default")
      (node (ref "PUENTE") (pin "N/C") (pinfunction "(N/C)_N/C") (pintype "bidirectional"))
    )
    (net (code "167") (name "unconnected-(PUENTE-0(RX)-Pad0)") (class "Default")
      (node (ref "PUENTE") (pin "0") (pinfunction "0(RX)_0") (pintype "bidirectional"))
    )
    (net (code "168") (name "unconnected-(PUENTE-1(TX)-Pad1)") (class "Default")
      (node (ref "PUENTE") (pin "1") (pinfunction "1(TX)_1") (pintype "bidirectional"))
    )
    (net (code "169") (name "unconnected-(PUENTE-27(SDA)-PadSDA)") (class "Default")
      (node (ref "PUENTE") (pin "SDA") (pinfunction "27(SDA)_SDA") (pintype "bidirectional"))
    )
    (net (code "170") (name "unconnected-(PUENTE-28(SCL)-PadSCL)") (class "Default")
      (node (ref "PUENTE") (pin "SCL") (pinfunction "28(SCL)_SCL") (pintype "bidirectional"))
    )
    (net (code "171") (name "unconnected-(PUENTE-IOREF-PadI{slash}OREF)") (class "Default")
      (node (ref "PUENTE") (pin "I/OREF") (pinfunction "IOREF_I/OREF") (pintype "bidirectional"))
    )
    (net (code "172") (name "unconnected-(PUENTE-Pad3.3V)") (class "Default")
      (node (ref "PUENTE") (pin "3.3V") (pinfunction "3.3V_3.3V") (pintype "bidirectional"))
    )
    (net (code "173") (name "unconnected-(PUENTE-Pad13)") (class "Default")
      (node (ref "PUENTE") (pin "13") (pinfunction "13_13") (pintype "bidirectional"))
    )
    (net (code "174") (name "unconnected-(PUENTE-PadA0)") (class "Default")
      (node (ref "PUENTE") (pin "A0") (pinfunction "A0_A0") (pintype "bidirectional"))
    )
    (net (code "175") (name "unconnected-(PUENTE-PadA1)") (class "Default")
      (node (ref "PUENTE") (pin "A1") (pinfunction "A1_A1") (pintype "bidirectional"))
    )
    (net (code "176") (name "unconnected-(PUENTE-PadA2)") (class "Default")
      (node (ref "PUENTE") (pin "A2") (pinfunction "A2_A2") (pintype "bidirectional"))
    )
    (net (code "177") (name "unconnected-(PUENTE-PadA3)") (class "Default")
      (node (ref "PUENTE") (pin "A3") (pinfunction "A3_A3") (pintype "bidirectional"))
    )
    (net (code "178") (name "unconnected-(PUENTE-PadA4)") (class "Default")
      (node (ref "PUENTE") (pin "A4") (pinfunction "A4_A4") (pintype "bidirectional"))
    )
    (net (code "179") (name "unconnected-(PUENTE-PadA5)") (class "Default")
      (node (ref "PUENTE") (pin "A5") (pinfunction "A5_A5") (pintype "bidirectional"))
    )
    (net (code "180") (name "unconnected-(PUENTE-PadAREF)") (class "Default")
      (node (ref "PUENTE") (pin "AREF") (pinfunction "AREF_AREF") (pintype "bidirectional"))
    )
    (net (code "181") (name "unconnected-(PUENTE-PadRESET)") (class "Default")
      (node (ref "PUENTE") (pin "RESET") (pinfunction "RESET_RESET") (pintype "bidirectional"))
    )
    (net (code "182") (name "unconnected-(PUENTE-PadVIN)") (class "Default")
      (node (ref "PUENTE") (pin "VIN") (pinfunction "VIN_VIN") (pintype "bidirectional"))
    )
    (net (code "183") (name "unconnected-(PUENTE-~{3}-Pad3)") (class "Default")
      (node (ref "PUENTE") (pin "3") (pinfunction "~{3}_3") (pintype "bidirectional"))
    )
    (net (code "184") (name "unconnected-(PUENTE-~{5}-Pad5)") (class "Default")
      (node (ref "PUENTE") (pin "5") (pinfunction "~{5}_5") (pintype "bidirectional"))
    )
    (net (code "185") (name "unconnected-(PUENTE-~{11}-Pad11)") (class "Default")
      (node (ref "PUENTE") (pin "11") (pinfunction "~{11}_11") (pintype "bidirectional"))
    )
    (net (code "186") (name "unconnected-(PUENTE2-(N{slash}C)-PadN{slash}C)") (class "Default")
      (node (ref "PUENTE2") (pin "N/C") (pinfunction "(N/C)_N/C") (pintype "bidirectional"))
    )
    (net (code "187") (name "unconnected-(PUENTE2-0(RX)-Pad0)") (class "Default")
      (node (ref "PUENTE2") (pin "0") (pinfunction "0(RX)_0") (pintype "bidirectional"))
    )
    (net (code "188") (name "unconnected-(PUENTE2-1(TX)-Pad1)") (class "Default")
      (node (ref "PUENTE2") (pin "1") (pinfunction "1(TX)_1") (pintype "bidirectional"))
    )
    (net (code "189") (name "unconnected-(PUENTE2-27(SDA)-PadSDA)") (class "Default")
      (node (ref "PUENTE2") (pin "SDA") (pinfunction "27(SDA)_SDA") (pintype "bidirectional"))
    )
    (net (code "190") (name "unconnected-(PUENTE2-28(SCL)-PadSCL)") (class "Default")
      (node (ref "PUENTE2") (pin "SCL") (pinfunction "28(SCL)_SCL") (pintype "bidirectional"))
    )
    (net (code "191") (name "unconnected-(PUENTE2-IOREF-PadI{slash}OREF)") (class "Default")
      (node (ref "PUENTE2") (pin "I/OREF") (pinfunction "IOREF_I/OREF") (pintype "bidirectional"))
    )
    (net (code "192") (name "unconnected-(PUENTE2-Pad3.3V)") (class "Default")
      (node (ref "PUENTE2") (pin "3.3V") (pinfunction "3.3V_3.3V") (pintype "bidirectional"))
    )
    (net (code "193") (name "unconnected-(PUENTE2-Pad13)") (class "Default")
      (node (ref "PUENTE2") (pin "13") (pinfunction "13_13") (pintype "bidirectional"))
    )
    (net (code "194") (name "unconnected-(PUENTE2-PadA0)") (class "Default")
      (node (ref "PUENTE2") (pin "A0") (pinfunction "A0_A0") (pintype "bidirectional"))
    )
    (net (code "195") (name "unconnected-(PUENTE2-PadA1)") (class "Default")
      (node (ref "PUENTE2") (pin "A1") (pinfunction "A1_A1") (pintype "bidirectional"))
    )
    (net (code "196") (name "unconnected-(PUENTE2-PadA2)") (class "Default")
      (node (ref "PUENTE2") (pin "A2") (pinfunction "A2_A2") (pintype "bidirectional"))
    )
    (net (code "197") (name "unconnected-(PUENTE2-PadA3)") (class "Default")
      (node (ref "PUENTE2") (pin "A3") (pinfunction "A3_A3") (pintype "bidirectional"))
    )
    (net (code "198") (name "unconnected-(PUENTE2-PadA4)") (class "Default")
      (node (ref "PUENTE2") (pin "A4") (pinfunction "A4_A4") (pintype "bidirectional"))
    )
    (net (code "199") (name "unconnected-(PUENTE2-PadA5)") (class "Default")
      (node (ref "PUENTE2") (pin "A5") (pinfunction "A5_A5") (pintype "bidirectional"))
    )
    (net (code "200") (name "unconnected-(PUENTE2-PadAREF)") (class "Default")
      (node (ref "PUENTE2") (pin "AREF") (pinfunction "AREF_AREF") (pintype "bidirectional"))
    )
    (net (code "201") (name "unconnected-(PUENTE2-PadRESET)") (class "Default")
      (node (ref "PUENTE2") (pin "RESET") (pinfunction "RESET_RESET") (pintype "bidirectional"))
    )
    (net (code "202") (name "unconnected-(PUENTE2-PadVIN)") (class "Default")
      (node (ref "PUENTE2") (pin "VIN") (pinfunction "VIN_VIN") (pintype "bidirectional"))
    )
    (net (code "203") (name "unconnected-(PUENTE2-~{3}-Pad3)") (class "Default")
      (node (ref "PUENTE2") (pin "3") (pinfunction "~{3}_3") (pintype "bidirectional"))
    )
    (net (code "204") (name "unconnected-(PUENTE2-~{5}-Pad5)") (class "Default")
      (node (ref "PUENTE2") (pin "5") (pinfunction "~{5}_5") (pintype "bidirectional"))
    )
    (net (code "205") (name "unconnected-(PUENTE2-~{11}-Pad11)") (class "Default")
      (node (ref "PUENTE2") (pin "11") (pinfunction "~{11}_11") (pintype "bidirectional"))
    )
  )
)
